# I2C_MUX.net
KiCad netlist of a schematic drawn in Altium Designer
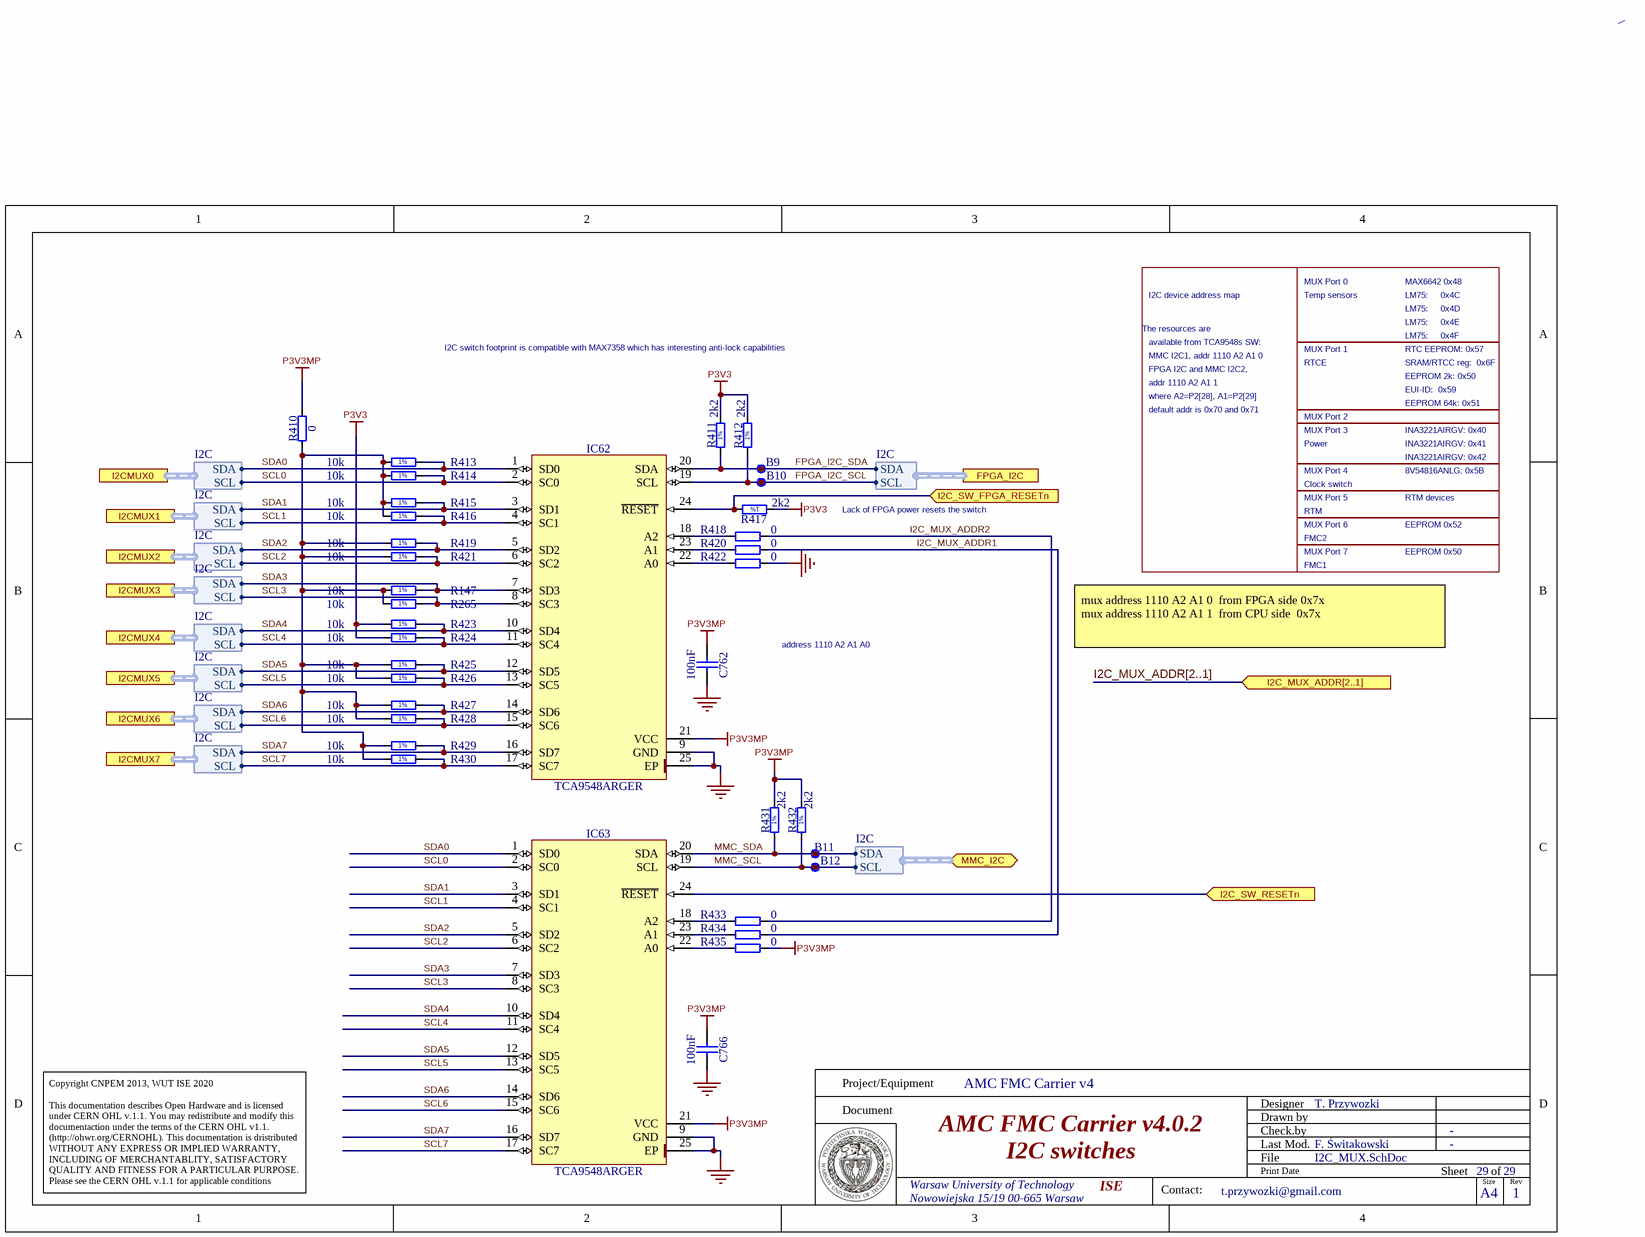
[diagram p0: I2C_MUX.SchDoc]

(export (version "E")
  (design (tool "Eeschema 10.0.6"))
  (components
    (comp (ref "B9")
      (value "SMD Pad")
      (footprint "C100")
      (description "Through Hole Pad")
      (fields (field (name "PART NUMBER") "SMD_PAD_D1MM") (field (name "AUTHOR") "CERN DEM JLC"))
      (libsource (lib "Eletro-mechanical") (part "Single SMD Pad (Round)"))
    )
    (comp (ref "B10")
      (value "SMD Pad")
      (footprint "C100")
      (description "Through Hole Pad")
      (fields (field (name "PART NUMBER") "SMD_PAD_D1MM") (field (name "AUTHOR") "CERN DEM JLC"))
      (libsource (lib "Eletro-mechanical") (part "Single SMD Pad (Round)"))
    )
    (comp (ref "B11")
      (value "SMD Pad")
      (footprint "C100")
      (description "Through Hole Pad")
      (fields (field (name "PART NUMBER") "SMD_PAD_D1MM") (field (name "AUTHOR") "CERN DEM JLC"))
      (libsource (lib "Eletro-mechanical") (part "Single SMD Pad (Round)"))
    )
    (comp (ref "B12")
      (value "SMD Pad")
      (footprint "C100")
      (description "Through Hole Pad")
      (fields (field (name "PART NUMBER") "SMD_PAD_D1MM") (field (name "AUTHOR") "CERN DEM JLC"))
      (libsource (lib "Eletro-mechanical") (part "Single SMD Pad (Round)"))
    )
    (comp (ref "C762")
      (value "100nF")
      (footprint "CAPC0603X33N")
      (description "Non-polarised capacitor")
      (fields
        (field (name "MANUFACTURER PART NUMBER") "CC0201_100NF_6.3V_10%_X5R")
        (field (name "MANUFACTURER") "GENERIC")
        (field (name "AUTHOR") "CERN DEM JLC")
      )
      (libsource (lib "Capacitors") (part "Capacitor - non polarized"))
    )
    (comp (ref "C766")
      (value "100nF")
      (footprint "CAPC0603X33N")
      (description "Non-polarised capacitor")
      (fields
        (field (name "MANUFACTURER PART NUMBER") "CC0201_100NF_6.3V_10%_X5R")
        (field (name "MANUFACTURER") "GENERIC")
        (field (name "AUTHOR") "CERN DEM JLC")
      )
      (libsource (lib "Capacitors") (part "Capacitor - non polarized"))
    )
    (comp (ref "IC62")
      (value "TCA9548ARGER")
      (footprint "QFN50P400X400X100-25N-S220")
      (description "Low Voltage 8-Channel I2C Switch With Reset")
      (fields (field (name "MANUFACTURER") "TEXAS INSTRUMENTS") (field (name "AUTHOR") "CERN DEM JLC"))
      (libsource (lib "ICs And Semiconductors") (part "TCA9548ARGER"))
    )
    (comp (ref "IC63")
      (value "TCA9548ARGER")
      (footprint "QFN50P400X400X100-25N-S220")
      (description "Low Voltage 8-Channel I2C Switch With Reset")
      (fields (field (name "MANUFACTURER") "TEXAS INSTRUMENTS") (field (name "AUTHOR") "CERN DEM JLC"))
      (libsource (lib "ICs And Semiconductors") (part "TCA9548ARGER"))
    )
    (comp (ref "R147")
      (value "10k")
      (footprint "RESC1005X40N")
      (description "Resistor - 1%")
      (fields
        (field (name "MANUFACTURER PART NUMBER") "R0402_10K_1%_0.0625W_100PPM")
        (field (name "MANUFACTURER") "GENERIC")
        (field (name "AUTHOR") "CERN DEM JLC")
      )
      (libsource (lib "Resistors") (part "Resistor - 1%"))
    )
    (comp (ref "R265")
      (value "10k")
      (footprint "RESC1005X40N")
      (description "Resistor - 1%")
      (fields
        (field (name "MANUFACTURER PART NUMBER") "R0402_10K_1%_0.0625W_100PPM")
        (field (name "MANUFACTURER") "GENERIC")
        (field (name "AUTHOR") "CERN DEM JLC")
      )
      (libsource (lib "Resistors") (part "Resistor - 1%"))
    )
    (comp (ref "R410")
      (value "0")
      (footprint "RESC1005X40N")
      (description "Resistor")
      (fields
        (field (name "MANUFACTURER PART NUMBER") "R0402_0R_JUMPER")
        (field (name "MANUFACTURER") "GENERIC")
        (field (name "AUTHOR") "CERN DEM JLC")
      )
      (libsource (lib "Resistors") (part "Resistor"))
    )
    (comp (ref "R411")
      (value "2k2")
      (footprint "RESC1005X40N")
      (description "Resistor - 1%")
      (fields
        (field (name "MANUFACTURER PART NUMBER") "R0402_2K2_1%_0.0625W_100PPM")
        (field (name "MANUFACTURER") "GENERIC")
        (field (name "AUTHOR") "CERN DEM JLC")
      )
      (libsource (lib "Resistors") (part "Resistor - 1%"))
    )
    (comp (ref "R412")
      (value "2k2")
      (footprint "RESC1005X40N")
      (description "Resistor - 1%")
      (fields
        (field (name "MANUFACTURER PART NUMBER") "R0402_2K2_1%_0.0625W_100PPM")
        (field (name "MANUFACTURER") "GENERIC")
        (field (name "AUTHOR") "CERN DEM JLC")
      )
      (libsource (lib "Resistors") (part "Resistor - 1%"))
    )
    (comp (ref "R413")
      (value "10k")
      (footprint "RESC1005X40N")
      (description "Resistor - 1%")
      (fields
        (field (name "MANUFACTURER PART NUMBER") "R0402_10K_1%_0.0625W_100PPM")
        (field (name "MANUFACTURER") "GENERIC")
        (field (name "AUTHOR") "CERN DEM JLC")
      )
      (libsource (lib "Resistors") (part "Resistor - 1%"))
    )
    (comp (ref "R414")
      (value "10k")
      (footprint "RESC1005X40N")
      (description "Resistor - 1%")
      (fields
        (field (name "MANUFACTURER PART NUMBER") "R0402_10K_1%_0.0625W_100PPM")
        (field (name "MANUFACTURER") "GENERIC")
        (field (name "AUTHOR") "CERN DEM JLC")
      )
      (libsource (lib "Resistors") (part "Resistor - 1%"))
    )
    (comp (ref "R415")
      (value "10k")
      (footprint "RESC1005X40N")
      (description "Resistor - 1%")
      (fields
        (field (name "MANUFACTURER PART NUMBER") "R0402_10K_1%_0.0625W_100PPM")
        (field (name "MANUFACTURER") "GENERIC")
        (field (name "AUTHOR") "CERN DEM JLC")
      )
      (libsource (lib "Resistors") (part "Resistor - 1%"))
    )
    (comp (ref "R416")
      (value "10k")
      (footprint "RESC1005X40N")
      (description "Resistor - 1%")
      (fields
        (field (name "MANUFACTURER PART NUMBER") "R0402_10K_1%_0.0625W_100PPM")
        (field (name "MANUFACTURER") "GENERIC")
        (field (name "AUTHOR") "CERN DEM JLC")
      )
      (libsource (lib "Resistors") (part "Resistor - 1%"))
    )
    (comp (ref "R417")
      (value "2k2")
      (footprint "RESC1005X40N")
      (description "Resistor - 1%")
      (fields
        (field (name "MANUFACTURER PART NUMBER") "R0402_2K2_1%_0.0625W_100PPM")
        (field (name "MANUFACTURER") "GENERIC")
        (field (name "AUTHOR") "CERN DEM JLC")
      )
      (libsource (lib "Resistors") (part "Resistor - 1%"))
    )
    (comp (ref "R418")
      (value "0")
      (footprint "RESC1005X40N")
      (description "Resistor")
      (fields
        (field (name "MANUFACTURER PART NUMBER") "R0402_0R_JUMPER")
        (field (name "MANUFACTURER") "GENERIC")
        (field (name "AUTHOR") "CERN DEM JLC")
      )
      (libsource (lib "Resistors") (part "Resistor"))
    )
    (comp (ref "R419")
      (value "10k")
      (footprint "RESC1005X40N")
      (description "Resistor - 1%")
      (fields
        (field (name "MANUFACTURER PART NUMBER") "R0402_10K_1%_0.0625W_100PPM")
        (field (name "MANUFACTURER") "GENERIC")
        (field (name "AUTHOR") "CERN DEM JLC")
      )
      (libsource (lib "Resistors") (part "Resistor - 1%"))
    )
    (comp (ref "R420")
      (value "0")
      (footprint "RESC1005X40N")
      (description "Resistor")
      (fields
        (field (name "MANUFACTURER PART NUMBER") "R0402_0R_JUMPER")
        (field (name "MANUFACTURER") "GENERIC")
        (field (name "AUTHOR") "CERN DEM JLC")
      )
      (libsource (lib "Resistors") (part "Resistor"))
    )
    (comp (ref "R421")
      (value "10k")
      (footprint "RESC1005X40N")
      (description "Resistor - 1%")
      (fields
        (field (name "MANUFACTURER PART NUMBER") "R0402_10K_1%_0.0625W_100PPM")
        (field (name "MANUFACTURER") "GENERIC")
        (field (name "AUTHOR") "CERN DEM JLC")
      )
      (libsource (lib "Resistors") (part "Resistor - 1%"))
    )
    (comp (ref "R422")
      (value "0")
      (footprint "RESC1005X40N")
      (description "Resistor")
      (fields
        (field (name "MANUFACTURER PART NUMBER") "R0402_0R_JUMPER")
        (field (name "MANUFACTURER") "GENERIC")
        (field (name "AUTHOR") "CERN DEM JLC")
      )
      (libsource (lib "Resistors") (part "Resistor"))
    )
    (comp (ref "R423")
      (value "10k")
      (footprint "RESC1005X40N")
      (description "Resistor - 1%")
      (fields
        (field (name "MANUFACTURER PART NUMBER") "R0402_10K_1%_0.0625W_100PPM")
        (field (name "MANUFACTURER") "GENERIC")
        (field (name "AUTHOR") "CERN DEM JLC")
      )
      (libsource (lib "Resistors") (part "Resistor - 1%"))
    )
    (comp (ref "R424")
      (value "10k")
      (footprint "RESC1005X40N")
      (description "Resistor - 1%")
      (fields
        (field (name "MANUFACTURER PART NUMBER") "R0402_10K_1%_0.0625W_100PPM")
        (field (name "MANUFACTURER") "GENERIC")
        (field (name "AUTHOR") "CERN DEM JLC")
      )
      (libsource (lib "Resistors") (part "Resistor - 1%"))
    )
    (comp (ref "R425")
      (value "10k")
      (footprint "RESC1005X40N")
      (description "Resistor - 1%")
      (fields
        (field (name "MANUFACTURER PART NUMBER") "R0402_10K_1%_0.0625W_100PPM")
        (field (name "MANUFACTURER") "GENERIC")
        (field (name "AUTHOR") "CERN DEM JLC")
      )
      (libsource (lib "Resistors") (part "Resistor - 1%"))
    )
    (comp (ref "R426")
      (value "10k")
      (footprint "RESC1005X40N")
      (description "Resistor - 1%")
      (fields
        (field (name "MANUFACTURER PART NUMBER") "R0402_10K_1%_0.0625W_100PPM")
        (field (name "MANUFACTURER") "GENERIC")
        (field (name "AUTHOR") "CERN DEM JLC")
      )
      (libsource (lib "Resistors") (part "Resistor - 1%"))
    )
    (comp (ref "R427")
      (value "10k")
      (footprint "RESC1005X40N")
      (description "Resistor - 1%")
      (fields
        (field (name "MANUFACTURER PART NUMBER") "R0402_10K_1%_0.0625W_100PPM")
        (field (name "MANUFACTURER") "GENERIC")
        (field (name "AUTHOR") "CERN DEM JLC")
      )
      (libsource (lib "Resistors") (part "Resistor - 1%"))
    )
    (comp (ref "R428")
      (value "10k")
      (footprint "RESC1005X40N")
      (description "Resistor - 1%")
      (fields
        (field (name "MANUFACTURER PART NUMBER") "R0402_10K_1%_0.0625W_100PPM")
        (field (name "MANUFACTURER") "GENERIC")
        (field (name "AUTHOR") "CERN DEM JLC")
      )
      (libsource (lib "Resistors") (part "Resistor - 1%"))
    )
    (comp (ref "R429")
      (value "10k")
      (footprint "RESC1005X40N")
      (description "Resistor - 1%")
      (fields
        (field (name "MANUFACTURER PART NUMBER") "R0402_10K_1%_0.0625W_100PPM")
        (field (name "MANUFACTURER") "GENERIC")
        (field (name "AUTHOR") "CERN DEM JLC")
      )
      (libsource (lib "Resistors") (part "Resistor - 1%"))
    )
    (comp (ref "R430")
      (value "10k")
      (footprint "RESC1005X40N")
      (description "Resistor - 1%")
      (fields
        (field (name "MANUFACTURER PART NUMBER") "R0402_10K_1%_0.0625W_100PPM")
        (field (name "MANUFACTURER") "GENERIC")
        (field (name "AUTHOR") "CERN DEM JLC")
      )
      (libsource (lib "Resistors") (part "Resistor - 1%"))
    )
    (comp (ref "R431")
      (value "2k2")
      (footprint "RESC1005X40N")
      (description "Resistor - 1%")
      (fields
        (field (name "MANUFACTURER PART NUMBER") "R0402_2K2_1%_0.0625W_100PPM")
        (field (name "MANUFACTURER") "GENERIC")
        (field (name "AUTHOR") "CERN DEM JLC")
      )
      (libsource (lib "Resistors") (part "Resistor - 1%"))
    )
    (comp (ref "R432")
      (value "2k2")
      (footprint "RESC1005X40N")
      (description "Resistor - 1%")
      (fields
        (field (name "MANUFACTURER PART NUMBER") "R0402_2K2_1%_0.0625W_100PPM")
        (field (name "MANUFACTURER") "GENERIC")
        (field (name "AUTHOR") "CERN DEM JLC")
      )
      (libsource (lib "Resistors") (part "Resistor - 1%"))
    )
    (comp (ref "R433")
      (value "0")
      (footprint "RESC1005X40N")
      (description "Resistor")
      (fields
        (field (name "MANUFACTURER PART NUMBER") "R0402_0R_JUMPER")
        (field (name "MANUFACTURER") "GENERIC")
        (field (name "AUTHOR") "CERN DEM JLC")
      )
      (libsource (lib "Resistors") (part "Resistor"))
    )
    (comp (ref "R434")
      (value "0")
      (footprint "RESC1005X40N")
      (description "Resistor")
      (fields
        (field (name "MANUFACTURER PART NUMBER") "R0402_0R_JUMPER")
        (field (name "MANUFACTURER") "GENERIC")
        (field (name "AUTHOR") "CERN DEM JLC")
      )
      (libsource (lib "Resistors") (part "Resistor"))
    )
    (comp (ref "R435")
      (value "0")
      (footprint "RESC1005X40N")
      (description "Resistor")
      (fields
        (field (name "MANUFACTURER PART NUMBER") "R0402_0R_JUMPER")
        (field (name "MANUFACTURER") "GENERIC")
        (field (name "AUTHOR") "CERN DEM JLC")
      )
      (libsource (lib "Resistors") (part "Resistor"))
    )
  )
  (nets
    (net (code "2") (name "/FPGA_I2C_SCL") (class "Default")
      (node (ref "B10") (pin "1") (pinfunction "1_1") (pintype "bidirectional"))
      (node (ref "IC62") (pin "19") (pinfunction "SCL_19") (pintype "bidirectional"))
      (node (ref "R412") (pin "1") (pinfunction "1_1") (pintype "passive"))
    )
    (net (code "3") (name "/FPGA_I2C_SDA") (class "Default")
      (node (ref "B9") (pin "1") (pinfunction "1_1") (pintype "bidirectional"))
      (node (ref "IC62") (pin "20") (pinfunction "SDA_20") (pintype "bidirectional"))
      (node (ref "R411") (pin "1") (pinfunction "1_1") (pintype "passive"))
    )
    (net (code "4") (name "/I2C_MUX_ADDR1") (class "Default")
      (node (ref "R420") (pin "1") (pinfunction "1_1") (pintype "passive"))
      (node (ref "R434") (pin "1") (pinfunction "1_1") (pintype "passive"))
    )
    (net (code "5") (name "/I2C_MUX_ADDR2") (class "Default")
      (node (ref "R418") (pin "1") (pinfunction "1_1") (pintype "passive"))
      (node (ref "R433") (pin "1") (pinfunction "1_1") (pintype "passive"))
    )
    (net (code "7") (name "/I2C_SW_FPGA_RESETn") (class "Default")
      (node (ref "IC62") (pin "24") (pinfunction "~{RESET}_24") (pintype "input"))
      (node (ref "R417") (pin "2") (pinfunction "2_2") (pintype "passive"))
    )
    (net (code "8") (name "/I2C_SW_RESETn") (class "Default")
      (node (ref "IC63") (pin "24") (pinfunction "~{RESET}_24") (pintype "input"))
    )
    (net (code "9") (name "/MMC_SCL") (class "Default")
      (node (ref "B12") (pin "1") (pinfunction "1_1") (pintype "bidirectional"))
      (node (ref "IC63") (pin "19") (pinfunction "SCL_19") (pintype "bidirectional"))
      (node (ref "R432") (pin "1") (pinfunction "1_1") (pintype "passive"))
    )
    (net (code "10") (name "/MMC_SDA") (class "Default")
      (node (ref "B11") (pin "1") (pinfunction "1_1") (pintype "bidirectional"))
      (node (ref "IC63") (pin "20") (pinfunction "SDA_20") (pintype "bidirectional"))
      (node (ref "R431") (pin "1") (pinfunction "1_1") (pintype "passive"))
    )
    (net (code "11") (name "/SCL0") (class "Default")
      (node (ref "IC62") (pin "2") (pinfunction "SC0_2") (pintype "bidirectional"))
      (node (ref "IC63") (pin "2") (pinfunction "SC0_2") (pintype "bidirectional"))
      (node (ref "R414") (pin "2") (pinfunction "2_2") (pintype "passive"))
    )
    (net (code "12") (name "/SCL1") (class "Default")
      (node (ref "IC62") (pin "4") (pinfunction "SC1_4") (pintype "bidirectional"))
      (node (ref "IC63") (pin "4") (pinfunction "SC1_4") (pintype "bidirectional"))
      (node (ref "R416") (pin "2") (pinfunction "2_2") (pintype "passive"))
    )
    (net (code "13") (name "/SCL2") (class "Default")
      (node (ref "IC62") (pin "6") (pinfunction "SC2_6") (pintype "bidirectional"))
      (node (ref "IC63") (pin "6") (pinfunction "SC2_6") (pintype "bidirectional"))
      (node (ref "R421") (pin "2") (pinfunction "2_2") (pintype "passive"))
    )
    (net (code "14") (name "/SCL3") (class "Default")
      (node (ref "IC62") (pin "8") (pinfunction "SC3_8") (pintype "bidirectional"))
      (node (ref "IC63") (pin "8") (pinfunction "SC3_8") (pintype "bidirectional"))
      (node (ref "R265") (pin "2") (pinfunction "2_2") (pintype "passive"))
    )
    (net (code "15") (name "/SCL4") (class "Default")
      (node (ref "IC62") (pin "11") (pinfunction "SC4_11") (pintype "bidirectional"))
      (node (ref "IC63") (pin "11") (pinfunction "SC4_11") (pintype "bidirectional"))
      (node (ref "R424") (pin "2") (pinfunction "2_2") (pintype "passive"))
    )
    (net (code "16") (name "/SCL5") (class "Default")
      (node (ref "IC62") (pin "13") (pinfunction "SC5_13") (pintype "bidirectional"))
      (node (ref "IC63") (pin "13") (pinfunction "SC5_13") (pintype "bidirectional"))
      (node (ref "R426") (pin "2") (pinfunction "2_2") (pintype "passive"))
    )
    (net (code "17") (name "/SCL6") (class "Default")
      (node (ref "IC62") (pin "15") (pinfunction "SC6_15") (pintype "bidirectional"))
      (node (ref "IC63") (pin "15") (pinfunction "SC6_15") (pintype "bidirectional"))
      (node (ref "R428") (pin "2") (pinfunction "2_2") (pintype "passive"))
    )
    (net (code "18") (name "/SCL7") (class "Default")
      (node (ref "IC62") (pin "17") (pinfunction "SC7_17") (pintype "bidirectional"))
      (node (ref "IC63") (pin "17") (pinfunction "SC7_17") (pintype "bidirectional"))
      (node (ref "R430") (pin "2") (pinfunction "2_2") (pintype "passive"))
    )
    (net (code "19") (name "/SDA0") (class "Default")
      (node (ref "IC62") (pin "1") (pinfunction "SD0_1") (pintype "bidirectional"))
      (node (ref "IC63") (pin "1") (pinfunction "SD0_1") (pintype "bidirectional"))
      (node (ref "R413") (pin "2") (pinfunction "2_2") (pintype "passive"))
    )
    (net (code "20") (name "/SDA1") (class "Default")
      (node (ref "IC62") (pin "3") (pinfunction "SD1_3") (pintype "bidirectional"))
      (node (ref "IC63") (pin "3") (pinfunction "SD1_3") (pintype "bidirectional"))
      (node (ref "R415") (pin "2") (pinfunction "2_2") (pintype "passive"))
    )
    (net (code "21") (name "/SDA2") (class "Default")
      (node (ref "IC62") (pin "5") (pinfunction "SD2_5") (pintype "bidirectional"))
      (node (ref "IC63") (pin "5") (pinfunction "SD2_5") (pintype "bidirectional"))
      (node (ref "R419") (pin "2") (pinfunction "2_2") (pintype "passive"))
    )
    (net (code "22") (name "/SDA3") (class "Default")
      (node (ref "IC62") (pin "7") (pinfunction "SD3_7") (pintype "bidirectional"))
      (node (ref "IC63") (pin "7") (pinfunction "SD3_7") (pintype "bidirectional"))
      (node (ref "R147") (pin "2") (pinfunction "2_2") (pintype "passive"))
    )
    (net (code "23") (name "/SDA4") (class "Default")
      (node (ref "IC62") (pin "10") (pinfunction "SD4_10") (pintype "bidirectional"))
      (node (ref "IC63") (pin "10") (pinfunction "SD4_10") (pintype "bidirectional"))
      (node (ref "R423") (pin "2") (pinfunction "2_2") (pintype "passive"))
    )
    (net (code "24") (name "/SDA5") (class "Default")
      (node (ref "IC62") (pin "12") (pinfunction "SD5_12") (pintype "bidirectional"))
      (node (ref "IC63") (pin "12") (pinfunction "SD5_12") (pintype "bidirectional"))
      (node (ref "R425") (pin "2") (pinfunction "2_2") (pintype "passive"))
    )
    (net (code "25") (name "/SDA6") (class "Default")
      (node (ref "IC62") (pin "14") (pinfunction "SD6_14") (pintype "bidirectional"))
      (node (ref "IC63") (pin "14") (pinfunction "SD6_14") (pintype "bidirectional"))
      (node (ref "R427") (pin "2") (pinfunction "2_2") (pintype "passive"))
    )
    (net (code "26") (name "/SDA7") (class "Default")
      (node (ref "IC62") (pin "16") (pinfunction "SD7_16") (pintype "bidirectional"))
      (node (ref "IC63") (pin "16") (pinfunction "SD7_16") (pintype "bidirectional"))
      (node (ref "R429") (pin "2") (pinfunction "2_2") (pintype "passive"))
    )
    (net (code "28") (name "GND") (class "Default")
      (node (ref "C762") (pin "2") (pinfunction "2_2") (pintype "passive"))
      (node (ref "C766") (pin "2") (pinfunction "2_2") (pintype "passive"))
      (node (ref "IC62") (pin "25") (pinfunction "EP_25") (pintype "power_in"))
      (node (ref "IC62") (pin "9") (pinfunction "GND_9") (pintype "power_in"))
      (node (ref "IC63") (pin "25") (pinfunction "EP_25") (pintype "power_in"))
      (node (ref "IC63") (pin "9") (pinfunction "GND_9") (pintype "power_in"))
      (node (ref "R422") (pin "1") (pinfunction "1_1") (pintype "passive"))
    )
    (net (code "29") (name "Net-(IC62-A0)") (class "Default")
      (node (ref "IC62") (pin "22") (pinfunction "A0_22") (pintype "input"))
      (node (ref "R422") (pin "2") (pinfunction "2_2") (pintype "passive"))
    )
    (net (code "30") (name "Net-(IC62-A1)") (class "Default")
      (node (ref "IC62") (pin "23") (pinfunction "A1_23") (pintype "input"))
      (node (ref "R420") (pin "2") (pinfunction "2_2") (pintype "passive"))
    )
    (net (code "31") (name "Net-(IC62-A2)") (class "Default")
      (node (ref "IC62") (pin "18") (pinfunction "A2_18") (pintype "input"))
      (node (ref "R418") (pin "2") (pinfunction "2_2") (pintype "passive"))
    )
    (net (code "32") (name "Net-(IC63-A0)") (class "Default")
      (node (ref "IC63") (pin "22") (pinfunction "A0_22") (pintype "input"))
      (node (ref "R435") (pin "2") (pinfunction "2_2") (pintype "passive"))
    )
    (net (code "33") (name "Net-(IC63-A1)") (class "Default")
      (node (ref "IC63") (pin "23") (pinfunction "A1_23") (pintype "input"))
      (node (ref "R434") (pin "2") (pinfunction "2_2") (pintype "passive"))
    )
    (net (code "34") (name "Net-(IC63-A2)") (class "Default")
      (node (ref "IC63") (pin "18") (pinfunction "A2_18") (pintype "input"))
      (node (ref "R433") (pin "2") (pinfunction "2_2") (pintype "passive"))
    )
    (net (code "35") (name "Net-(R147-Pad1)") (class "Default")
      (node (ref "R147") (pin "1") (pinfunction "1_1") (pintype "passive"))
      (node (ref "R265") (pin "1") (pinfunction "1_1") (pintype "passive"))
      (node (ref "R410") (pin "2") (pinfunction "2_2") (pintype "passive"))
      (node (ref "R413") (pin "1") (pinfunction "1_1") (pintype "passive"))
      (node (ref "R414") (pin "1") (pinfunction "1_1") (pintype "passive"))
      (node (ref "R415") (pin "1") (pinfunction "1_1") (pintype "passive"))
      (node (ref "R416") (pin "1") (pinfunction "1_1") (pintype "passive"))
      (node (ref "R419") (pin "1") (pinfunction "1_1") (pintype "passive"))
      (node (ref "R421") (pin "1") (pinfunction "1_1") (pintype "passive"))
      (node (ref "R425") (pin "1") (pinfunction "1_1") (pintype "passive"))
      (node (ref "R426") (pin "1") (pinfunction "1_1") (pintype "passive"))
      (node (ref "R427") (pin "1") (pinfunction "1_1") (pintype "passive"))
      (node (ref "R428") (pin "1") (pinfunction "1_1") (pintype "passive"))
      (node (ref "R429") (pin "1") (pinfunction "1_1") (pintype "passive"))
      (node (ref "R430") (pin "1") (pinfunction "1_1") (pintype "passive"))
    )
    (net (code "36") (name "P3V3") (class "Default")
      (node (ref "R411") (pin "2") (pinfunction "2_2") (pintype "passive"))
      (node (ref "R412") (pin "2") (pinfunction "2_2") (pintype "passive"))
      (node (ref "R417") (pin "1") (pinfunction "1_1") (pintype "passive"))
      (node (ref "R423") (pin "1") (pinfunction "1_1") (pintype "passive"))
      (node (ref "R424") (pin "1") (pinfunction "1_1") (pintype "passive"))
    )
    (net (code "37") (name "P3V3MP") (class "Default")
      (node (ref "C762") (pin "1") (pinfunction "1_1") (pintype "passive"))
      (node (ref "C766") (pin "1") (pinfunction "1_1") (pintype "passive"))
      (node (ref "IC62") (pin "21") (pinfunction "VCC_21") (pintype "power_in"))
      (node (ref "IC63") (pin "21") (pinfunction "VCC_21") (pintype "power_in"))
      (node (ref "R410") (pin "1") (pinfunction "1_1") (pintype "passive"))
      (node (ref "R431") (pin "2") (pinfunction "2_2") (pintype "passive"))
      (node (ref "R432") (pin "2") (pinfunction "2_2") (pintype "passive"))
      (node (ref "R435") (pin "1") (pinfunction "1_1") (pintype "passive"))
    )
  )
)
